# pinball-mega-shield.net
KiCad netlist of a schematic drawn in EAGLE
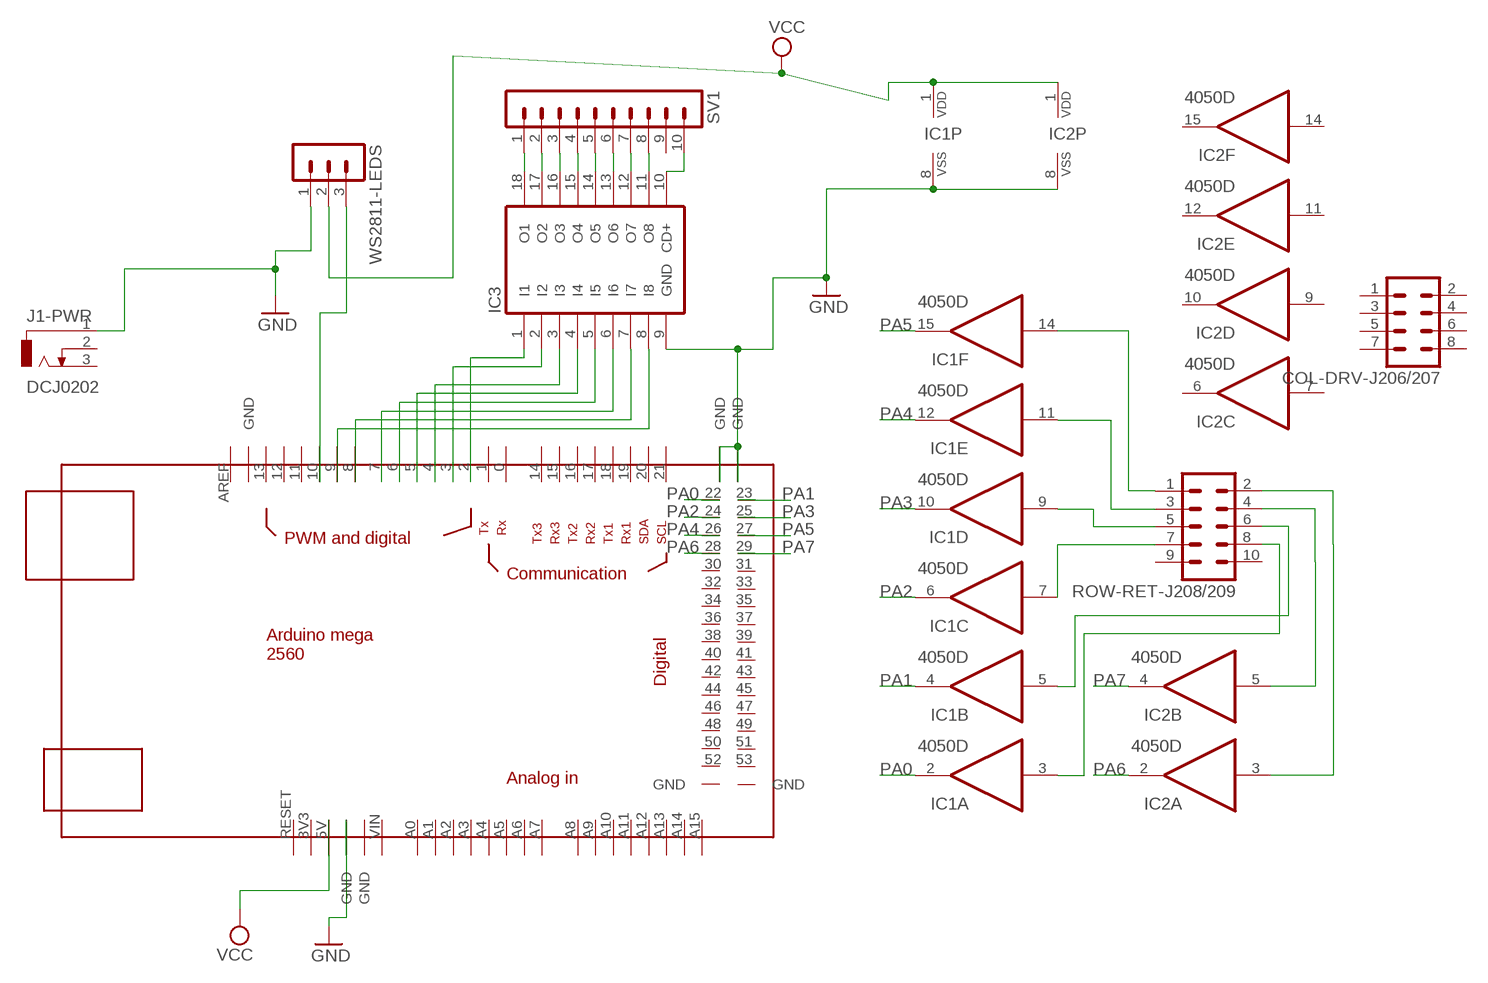
[diagram p0: schematic, sheet 1]

(export (version "E")
  (design (tool "Eeschema 10.0.6"))
  (components
    (comp (ref "COL-DRV-J206/207")
      (value "MA04-2")
      (footprint "eagle-import:MA04-2")
      (libsource (lib "eagle-import") (part "MA04-2"))
    )
    (comp (ref "IC1")
      (value "4050D")
      (footprint "eagle-import:SO16")
      (libsource (lib "eagle-import") (part "4050D"))
    )
    (comp (ref "IC2")
      (value "4050D")
      (footprint "eagle-import:SO16")
      (libsource (lib "eagle-import") (part "4050D"))
    )
    (comp (ref "IC3")
      (value "ULN2803A")
      (footprint "eagle-import:DIL18")
      (libsource (lib "eagle-import") (part "ULN2803A"))
    )
    (comp (ref "J1-PWR")
      (value "DCJ0202")
      (footprint "eagle-import:DCJ0202")
      (libsource (lib "eagle-import") (part "DCJ0202"))
    )
    (comp (ref "ROW-RET-J208/209")
      (value "MA05-2")
      (footprint "eagle-import:MA05-2")
      (libsource (lib "eagle-import") (part "MA05-2"))
    )
    (comp (ref "SV1")
      (value "MA10-1")
      (footprint "eagle-import:MA10-1")
      (libsource (lib "eagle-import") (part "MA10-1"))
    )
    (comp (ref "U$1")
      (value "MEGA_DEVICE")
      (footprint "eagle-import:MEGAOUTLINE")
      (libsource (lib "eagle-import") (part "MEGA_DEVICE"))
    )
    (comp (ref "WS2811-LEDS")
      (value "MA03-1")
      (footprint "eagle-import:MA03-1")
      (libsource (lib "eagle-import") (part "MA03-1"))
    )
  )
  (nets
    (net (code "1") (name "/PA0") (class "Default")
      (node (ref "IC1") (pin "2") (pinfunction "O_2") (pintype "output"))
      (node (ref "U$1") (pin "22") (pinfunction "22_22") (pintype "bidirectional"))
    )
    (net (code "2") (name "/PA1") (class "Default")
      (node (ref "IC1") (pin "4") (pinfunction "O_4") (pintype "output"))
      (node (ref "U$1") (pin "23") (pinfunction "23_23") (pintype "bidirectional"))
    )
    (net (code "3") (name "/PA2") (class "Default")
      (node (ref "IC1") (pin "6") (pinfunction "O_6") (pintype "output"))
      (node (ref "U$1") (pin "24") (pinfunction "24_24") (pintype "bidirectional"))
    )
    (net (code "4") (name "/PA3") (class "Default")
      (node (ref "IC1") (pin "10") (pinfunction "O_10") (pintype "output"))
      (node (ref "U$1") (pin "25") (pinfunction "25_25") (pintype "bidirectional"))
    )
    (net (code "5") (name "/PA4") (class "Default")
      (node (ref "IC1") (pin "12") (pinfunction "O_12") (pintype "output"))
      (node (ref "U$1") (pin "26") (pinfunction "26_26") (pintype "bidirectional"))
    )
    (net (code "6") (name "/PA5") (class "Default")
      (node (ref "IC1") (pin "15") (pinfunction "O_15") (pintype "output"))
      (node (ref "U$1") (pin "27") (pinfunction "27_27") (pintype "bidirectional"))
    )
    (net (code "7") (name "/PA6") (class "Default")
      (node (ref "IC2") (pin "2") (pinfunction "O_2") (pintype "output"))
      (node (ref "U$1") (pin "28") (pinfunction "28_28") (pintype "bidirectional"))
    )
    (net (code "8") (name "/PA7") (class "Default")
      (node (ref "IC2") (pin "4") (pinfunction "O_4") (pintype "output"))
      (node (ref "U$1") (pin "29") (pinfunction "29_29") (pintype "bidirectional"))
    )
    (net (code "9") (name "GND") (class "Default")
      (node (ref "IC1") (pin "8") (pinfunction "VSS_8") (pintype "power_in"))
      (node (ref "IC2") (pin "8") (pinfunction "VSS_8") (pintype "power_in"))
      (node (ref "IC3") (pin "9") (pinfunction "GND_9") (pintype "power_in"))
      (node (ref "J1-PWR") (pin "1") (pinfunction "1_1") (pintype "passive"))
      (node (ref "U$1") (pin "GND@2") (pinfunction "GND_GND@2") (pintype "bidirectional"))
      (node (ref "U$1") (pin "GND@4") (pinfunction "GND_GND@4") (pintype "bidirectional"))
      (node (ref "U$1") (pin "GND@5") (pinfunction "GND_GND@5") (pintype "bidirectional"))
      (node (ref "WS2811-LEDS") (pin "1") (pinfunction "1_1") (pintype "passive"))
    )
    (net (code "10") (name "Net-(IC1A-I)") (class "Default")
      (node (ref "IC1") (pin "3") (pinfunction "I_3") (pintype "input"))
      (node (ref "ROW-RET-J208/209") (pin "8") (pinfunction "8_8") (pintype "passive"))
    )
    (net (code "11") (name "Net-(IC1B-I)") (class "Default")
      (node (ref "IC1") (pin "5") (pinfunction "I_5") (pintype "input"))
      (node (ref "ROW-RET-J208/209") (pin "6") (pinfunction "6_6") (pintype "passive"))
    )
    (net (code "12") (name "Net-(IC1C-I)") (class "Default")
      (node (ref "IC1") (pin "7") (pinfunction "I_7") (pintype "input"))
      (node (ref "ROW-RET-J208/209") (pin "7") (pinfunction "7_7") (pintype "passive"))
    )
    (net (code "13") (name "Net-(IC1D-I)") (class "Default")
      (node (ref "IC1") (pin "9") (pinfunction "I_9") (pintype "input"))
      (node (ref "ROW-RET-J208/209") (pin "5") (pinfunction "5_5") (pintype "passive"))
    )
    (net (code "14") (name "Net-(IC1E-I)") (class "Default")
      (node (ref "IC1") (pin "11") (pinfunction "I_11") (pintype "input"))
      (node (ref "ROW-RET-J208/209") (pin "3") (pinfunction "3_3") (pintype "passive"))
    )
    (net (code "15") (name "Net-(IC1F-I)") (class "Default")
      (node (ref "IC1") (pin "14") (pinfunction "I_14") (pintype "input"))
      (node (ref "ROW-RET-J208/209") (pin "1") (pinfunction "1_1") (pintype "passive"))
    )
    (net (code "16") (name "Net-(IC2A-I)") (class "Default")
      (node (ref "IC2") (pin "3") (pinfunction "I_3") (pintype "input"))
      (node (ref "ROW-RET-J208/209") (pin "2") (pinfunction "2_2") (pintype "passive"))
    )
    (net (code "17") (name "Net-(IC2B-I)") (class "Default")
      (node (ref "IC2") (pin "5") (pinfunction "I_5") (pintype "input"))
      (node (ref "ROW-RET-J208/209") (pin "4") (pinfunction "4_4") (pintype "passive"))
    )
    (net (code "18") (name "Net-(IC3-CD+)") (class "Default")
      (node (ref "IC3") (pin "10") (pinfunction "CD+_10") (pintype "passive"))
      (node (ref "SV1") (pin "10") (pinfunction "10_10") (pintype "passive"))
    )
    (net (code "19") (name "Net-(IC3-I1)") (class "Default")
      (node (ref "IC3") (pin "1") (pinfunction "I1_1") (pintype "input"))
      (node (ref "U$1") (pin "2") (pinfunction "2_2") (pintype "bidirectional"))
    )
    (net (code "20") (name "Net-(IC3-I2)") (class "Default")
      (node (ref "IC3") (pin "2") (pinfunction "I2_2") (pintype "input"))
      (node (ref "U$1") (pin "3") (pinfunction "3_3") (pintype "bidirectional"))
    )
    (net (code "21") (name "Net-(IC3-I3)") (class "Default")
      (node (ref "IC3") (pin "3") (pinfunction "I3_3") (pintype "input"))
      (node (ref "U$1") (pin "4") (pinfunction "4_4") (pintype "bidirectional"))
    )
    (net (code "22") (name "Net-(IC3-I4)") (class "Default")
      (node (ref "IC3") (pin "4") (pinfunction "I4_4") (pintype "input"))
      (node (ref "U$1") (pin "5") (pinfunction "5_5") (pintype "bidirectional"))
    )
    (net (code "23") (name "Net-(IC3-I5)") (class "Default")
      (node (ref "IC3") (pin "5") (pinfunction "I5_5") (pintype "input"))
      (node (ref "U$1") (pin "6") (pinfunction "6_6") (pintype "bidirectional"))
    )
    (net (code "24") (name "Net-(IC3-I6)") (class "Default")
      (node (ref "IC3") (pin "6") (pinfunction "I6_6") (pintype "input"))
      (node (ref "U$1") (pin "7") (pinfunction "7_7") (pintype "bidirectional"))
    )
    (net (code "25") (name "Net-(IC3-I7)") (class "Default")
      (node (ref "IC3") (pin "7") (pinfunction "I7_7") (pintype "input"))
      (node (ref "U$1") (pin "8") (pinfunction "8_8") (pintype "bidirectional"))
    )
    (net (code "26") (name "Net-(IC3-I8)") (class "Default")
      (node (ref "IC3") (pin "8") (pinfunction "I8_8") (pintype "input"))
      (node (ref "U$1") (pin "9") (pinfunction "9_9") (pintype "bidirectional"))
    )
    (net (code "27") (name "Net-(IC3-O1)") (class "Default")
      (node (ref "IC3") (pin "18") (pinfunction "O1_18") (pintype "open_collector"))
      (node (ref "SV1") (pin "1") (pinfunction "1_1") (pintype "passive"))
    )
    (net (code "28") (name "Net-(IC3-O2)") (class "Default")
      (node (ref "IC3") (pin "17") (pinfunction "O2_17") (pintype "open_collector"))
      (node (ref "SV1") (pin "2") (pinfunction "2_2") (pintype "passive"))
    )
    (net (code "29") (name "Net-(IC3-O3)") (class "Default")
      (node (ref "IC3") (pin "16") (pinfunction "O3_16") (pintype "open_collector"))
      (node (ref "SV1") (pin "3") (pinfunction "3_3") (pintype "passive"))
    )
    (net (code "30") (name "Net-(IC3-O4)") (class "Default")
      (node (ref "IC3") (pin "15") (pinfunction "O4_15") (pintype "open_collector"))
      (node (ref "SV1") (pin "4") (pinfunction "4_4") (pintype "passive"))
    )
    (net (code "31") (name "Net-(IC3-O5)") (class "Default")
      (node (ref "IC3") (pin "14") (pinfunction "O5_14") (pintype "open_collector"))
      (node (ref "SV1") (pin "5") (pinfunction "5_5") (pintype "passive"))
    )
    (net (code "32") (name "Net-(IC3-O6)") (class "Default")
      (node (ref "IC3") (pin "13") (pinfunction "O6_13") (pintype "open_collector"))
      (node (ref "SV1") (pin "6") (pinfunction "6_6") (pintype "passive"))
    )
    (net (code "33") (name "Net-(IC3-O7)") (class "Default")
      (node (ref "IC3") (pin "12") (pinfunction "O7_12") (pintype "open_collector"))
      (node (ref "SV1") (pin "7") (pinfunction "7_7") (pintype "passive"))
    )
    (net (code "34") (name "Net-(IC3-O8)") (class "Default")
      (node (ref "IC3") (pin "11") (pinfunction "O8_11") (pintype "open_collector"))
      (node (ref "SV1") (pin "8") (pinfunction "8_8") (pintype "passive"))
    )
    (net (code "35") (name "Net-(U$1-Pad10)") (class "Default")
      (node (ref "U$1") (pin "10") (pinfunction "10_10") (pintype "bidirectional"))
      (node (ref "WS2811-LEDS") (pin "3") (pinfunction "3_3") (pintype "passive"))
    )
    (net (code "36") (name "VCC") (class "Default")
      (node (ref "IC1") (pin "1") (pinfunction "VDD_1") (pintype "power_in"))
      (node (ref "IC2") (pin "1") (pinfunction "VDD_1") (pintype "power_in"))
      (node (ref "U$1") (pin "5V") (pinfunction "5V_5V") (pintype "bidirectional"))
      (node (ref "WS2811-LEDS") (pin "2") (pinfunction "2_2") (pintype "passive"))
    )
    (net (code "37") (name "unconnected-(COL-DRV-J206/207-Pad1)") (class "Default")
      (node (ref "COL-DRV-J206/207") (pin "1") (pinfunction "1_1") (pintype "passive"))
    )
    (net (code "38") (name "unconnected-(COL-DRV-J206/207-Pad2)") (class "Default")
      (node (ref "COL-DRV-J206/207") (pin "2") (pinfunction "2_2") (pintype "passive"))
    )
    (net (code "39") (name "unconnected-(COL-DRV-J206/207-Pad3)") (class "Default")
      (node (ref "COL-DRV-J206/207") (pin "3") (pinfunction "3_3") (pintype "passive"))
    )
    (net (code "40") (name "unconnected-(COL-DRV-J206/207-Pad4)") (class "Default")
      (node (ref "COL-DRV-J206/207") (pin "4") (pinfunction "4_4") (pintype "passive"))
    )
    (net (code "41") (name "unconnected-(COL-DRV-J206/207-Pad5)") (class "Default")
      (node (ref "COL-DRV-J206/207") (pin "5") (pinfunction "5_5") (pintype "passive"))
    )
    (net (code "42") (name "unconnected-(COL-DRV-J206/207-Pad6)") (class "Default")
      (node (ref "COL-DRV-J206/207") (pin "6") (pinfunction "6_6") (pintype "passive"))
    )
    (net (code "43") (name "unconnected-(COL-DRV-J206/207-Pad7)") (class "Default")
      (node (ref "COL-DRV-J206/207") (pin "7") (pinfunction "7_7") (pintype "passive"))
    )
    (net (code "44") (name "unconnected-(COL-DRV-J206/207-Pad8)") (class "Default")
      (node (ref "COL-DRV-J206/207") (pin "8") (pinfunction "8_8") (pintype "passive"))
    )
    (net (code "45") (name "unconnected-(IC2C-I-Pad7)") (class "Default")
      (node (ref "IC2") (pin "7") (pinfunction "I_7") (pintype "input"))
    )
    (net (code "46") (name "unconnected-(IC2C-O-Pad6)") (class "Default")
      (node (ref "IC2") (pin "6") (pinfunction "O_6") (pintype "output"))
    )
    (net (code "47") (name "unconnected-(IC2D-I-Pad9)") (class "Default")
      (node (ref "IC2") (pin "9") (pinfunction "I_9") (pintype "input"))
    )
    (net (code "48") (name "unconnected-(IC2D-O-Pad10)") (class "Default")
      (node (ref "IC2") (pin "10") (pinfunction "O_10") (pintype "output"))
    )
    (net (code "49") (name "unconnected-(IC2E-I-Pad11)") (class "Default")
      (node (ref "IC2") (pin "11") (pinfunction "I_11") (pintype "input"))
    )
    (net (code "50") (name "unconnected-(IC2E-O-Pad12)") (class "Default")
      (node (ref "IC2") (pin "12") (pinfunction "O_12") (pintype "output"))
    )
    (net (code "51") (name "unconnected-(IC2F-I-Pad14)") (class "Default")
      (node (ref "IC2") (pin "14") (pinfunction "I_14") (pintype "input"))
    )
    (net (code "52") (name "unconnected-(IC2F-O-Pad15)") (class "Default")
      (node (ref "IC2") (pin "15") (pinfunction "O_15") (pintype "output"))
    )
    (net (code "53") (name "unconnected-(J1-PWR-Pad2)") (class "Default")
      (node (ref "J1-PWR") (pin "2") (pinfunction "2_2") (pintype "passive"))
    )
    (net (code "54") (name "unconnected-(J1-PWR-Pad3)") (class "Default")
      (node (ref "J1-PWR") (pin "3") (pinfunction "3_3") (pintype "passive"))
    )
    (net (code "55") (name "unconnected-(ROW-RET-J208/209-Pad9)") (class "Default")
      (node (ref "ROW-RET-J208/209") (pin "9") (pinfunction "9_9") (pintype "passive"))
    )
    (net (code "56") (name "unconnected-(ROW-RET-J208/209-Pad10)") (class "Default")
      (node (ref "ROW-RET-J208/209") (pin "10") (pinfunction "10_10") (pintype "passive"))
    )
    (net (code "57") (name "unconnected-(SV1-Pad9)") (class "Default")
      (node (ref "SV1") (pin "9") (pinfunction "9_9") (pintype "passive"))
    )
    (net (code "58") (name "unconnected-(U$1-GND-PadGND@1)") (class "Default")
      (node (ref "U$1") (pin "GND@1") (pinfunction "GND_GND@1") (pintype "bidirectional"))
    )
    (net (code "59") (name "unconnected-(U$1-GND-PadGND@3)") (class "Default")
      (node (ref "U$1") (pin "GND@3") (pinfunction "GND_GND@3") (pintype "bidirectional"))
    )
    (net (code "60") (name "unconnected-(U$1-GND-PadGND@6)") (class "Default")
      (node (ref "U$1") (pin "GND@6") (pinfunction "GND_GND@6") (pintype "bidirectional"))
    )
    (net (code "61") (name "unconnected-(U$1-GND-PadGND@7)") (class "Default")
      (node (ref "U$1") (pin "GND@7") (pinfunction "GND_GND@7") (pintype "bidirectional"))
    )
    (net (code "62") (name "unconnected-(U$1-Pad0)") (class "Default")
      (node (ref "U$1") (pin "0") (pinfunction "0_0") (pintype "bidirectional"))
    )
    (net (code "63") (name "unconnected-(U$1-Pad1)") (class "Default")
      (node (ref "U$1") (pin "1") (pinfunction "1_1") (pintype "bidirectional"))
    )
    (net (code "64") (name "unconnected-(U$1-Pad3V3)") (class "Default")
      (node (ref "U$1") (pin "3V3") (pinfunction "3V3_3V3") (pintype "bidirectional"))
    )
    (net (code "65") (name "unconnected-(U$1-Pad11)") (class "Default")
      (node (ref "U$1") (pin "11") (pinfunction "11_11") (pintype "bidirectional"))
    )
    (net (code "66") (name "unconnected-(U$1-Pad12)") (class "Default")
      (node (ref "U$1") (pin "12") (pinfunction "12_12") (pintype "bidirectional"))
    )
    (net (code "67") (name "unconnected-(U$1-Pad13)") (class "Default")
      (node (ref "U$1") (pin "13") (pinfunction "13_13") (pintype "bidirectional"))
    )
    (net (code "68") (name "unconnected-(U$1-Pad14)") (class "Default")
      (node (ref "U$1") (pin "14") (pinfunction "14_14") (pintype "bidirectional"))
    )
    (net (code "69") (name "unconnected-(U$1-Pad15)") (class "Default")
      (node (ref "U$1") (pin "15") (pinfunction "15_15") (pintype "bidirectional"))
    )
    (net (code "70") (name "unconnected-(U$1-Pad16)") (class "Default")
      (node (ref "U$1") (pin "16") (pinfunction "16_16") (pintype "bidirectional"))
    )
    (net (code "71") (name "unconnected-(U$1-Pad17)") (class "Default")
      (node (ref "U$1") (pin "17") (pinfunction "17_17") (pintype "bidirectional"))
    )
    (net (code "72") (name "unconnected-(U$1-Pad18)") (class "Default")
      (node (ref "U$1") (pin "18") (pinfunction "18_18") (pintype "bidirectional"))
    )
    (net (code "73") (name "unconnected-(U$1-Pad19)") (class "Default")
      (node (ref "U$1") (pin "19") (pinfunction "19_19") (pintype "bidirectional"))
    )
    (net (code "74") (name "unconnected-(U$1-Pad20)") (class "Default")
      (node (ref "U$1") (pin "20") (pinfunction "20_20") (pintype "bidirectional"))
    )
    (net (code "75") (name "unconnected-(U$1-Pad21)") (class "Default")
      (node (ref "U$1") (pin "21") (pinfunction "21_21") (pintype "bidirectional"))
    )
    (net (code "76") (name "unconnected-(U$1-Pad30)") (class "Default")
      (node (ref "U$1") (pin "30") (pinfunction "30_30") (pintype "bidirectional"))
    )
    (net (code "77") (name "unconnected-(U$1-Pad31)") (class "Default")
      (node (ref "U$1") (pin "31") (pinfunction "31_31") (pintype "bidirectional"))
    )
    (net (code "78") (name "unconnected-(U$1-Pad32)") (class "Default")
      (node (ref "U$1") (pin "32") (pinfunction "32_32") (pintype "bidirectional"))
    )
    (net (code "79") (name "unconnected-(U$1-Pad33)") (class "Default")
      (node (ref "U$1") (pin "33") (pinfunction "33_33") (pintype "bidirectional"))
    )
    (net (code "80") (name "unconnected-(U$1-Pad34)") (class "Default")
      (node (ref "U$1") (pin "34") (pinfunction "34_34") (pintype "bidirectional"))
    )
    (net (code "81") (name "unconnected-(U$1-Pad35)") (class "Default")
      (node (ref "U$1") (pin "35") (pinfunction "35_35") (pintype "bidirectional"))
    )
    (net (code "82") (name "unconnected-(U$1-Pad36)") (class "Default")
      (node (ref "U$1") (pin "36") (pinfunction "36_36") (pintype "bidirectional"))
    )
    (net (code "83") (name "unconnected-(U$1-Pad37)") (class "Default")
      (node (ref "U$1") (pin "37") (pinfunction "37_37") (pintype "bidirectional"))
    )
    (net (code "84") (name "unconnected-(U$1-Pad38)") (class "Default")
      (node (ref "U$1") (pin "38") (pinfunction "38_38") (pintype "bidirectional"))
    )
    (net (code "85") (name "unconnected-(U$1-Pad39)") (class "Default")
      (node (ref "U$1") (pin "39") (pinfunction "39_39") (pintype "bidirectional"))
    )
    (net (code "86") (name "unconnected-(U$1-Pad40)") (class "Default")
      (node (ref "U$1") (pin "40") (pinfunction "40_40") (pintype "bidirectional"))
    )
    (net (code "87") (name "unconnected-(U$1-Pad41)") (class "Default")
      (node (ref "U$1") (pin "41") (pinfunction "41_41") (pintype "bidirectional"))
    )
    (net (code "88") (name "unconnected-(U$1-Pad42)") (class "Default")
      (node (ref "U$1") (pin "42") (pinfunction "42_42") (pintype "bidirectional"))
    )
    (net (code "89") (name "unconnected-(U$1-Pad43)") (class "Default")
      (node (ref "U$1") (pin "43") (pinfunction "43_43") (pintype "bidirectional"))
    )
    (net (code "90") (name "unconnected-(U$1-Pad44)") (class "Default")
      (node (ref "U$1") (pin "44") (pinfunction "44_44") (pintype "bidirectional"))
    )
    (net (code "91") (name "unconnected-(U$1-Pad45)") (class "Default")
      (node (ref "U$1") (pin "45") (pinfunction "45_45") (pintype "bidirectional"))
    )
    (net (code "92") (name "unconnected-(U$1-Pad46)") (class "Default")
      (node (ref "U$1") (pin "46") (pinfunction "46_46") (pintype "bidirectional"))
    )
    (net (code "93") (name "unconnected-(U$1-Pad47)") (class "Default")
      (node (ref "U$1") (pin "47") (pinfunction "47_47") (pintype "bidirectional"))
    )
    (net (code "94") (name "unconnected-(U$1-Pad48)") (class "Default")
      (node (ref "U$1") (pin "48") (pinfunction "48_48") (pintype "bidirectional"))
    )
    (net (code "95") (name "unconnected-(U$1-Pad49)") (class "Default")
      (node (ref "U$1") (pin "49") (pinfunction "49_49") (pintype "bidirectional"))
    )
    (net (code "96") (name "unconnected-(U$1-Pad50)") (class "Default")
      (node (ref "U$1") (pin "50") (pinfunction "50_50") (pintype "bidirectional"))
    )
    (net (code "97") (name "unconnected-(U$1-Pad51)") (class "Default")
      (node (ref "U$1") (pin "51") (pinfunction "51_51") (pintype "bidirectional"))
    )
    (net (code "98") (name "unconnected-(U$1-Pad52)") (class "Default")
      (node (ref "U$1") (pin "52") (pinfunction "52_52") (pintype "bidirectional"))
    )
    (net (code "99") (name "unconnected-(U$1-Pad53)") (class "Default")
      (node (ref "U$1") (pin "53") (pinfunction "53_53") (pintype "bidirectional"))
    )
    (net (code "100") (name "unconnected-(U$1-PadA0)") (class "Default")
      (node (ref "U$1") (pin "A0") (pinfunction "A0_A0") (pintype "bidirectional"))
    )
    (net (code "101") (name "unconnected-(U$1-PadA1)") (class "Default")
      (node (ref "U$1") (pin "A1") (pinfunction "A1_A1") (pintype "bidirectional"))
    )
    (net (code "102") (name "unconnected-(U$1-PadA2)") (class "Default")
      (node (ref "U$1") (pin "A2") (pinfunction "A2_A2") (pintype "bidirectional"))
    )
    (net (code "103") (name "unconnected-(U$1-PadA3)") (class "Default")
      (node (ref "U$1") (pin "A3") (pinfunction "A3_A3") (pintype "bidirectional"))
    )
    (net (code "104") (name "unconnected-(U$1-PadA4)") (class "Default")
      (node (ref "U$1") (pin "A4") (pinfunction "A4_A4") (pintype "bidirectional"))
    )
    (net (code "105") (name "unconnected-(U$1-PadA5)") (class "Default")
      (node (ref "U$1") (pin "A5") (pinfunction "A5_A5") (pintype "bidirectional"))
    )
    (net (code "106") (name "unconnected-(U$1-PadA6)") (class "Default")
      (node (ref "U$1") (pin "A6") (pinfunction "A6_A6") (pintype "bidirectional"))
    )
    (net (code "107") (name "unconnected-(U$1-PadA7)") (class "Default")
      (node (ref "U$1") (pin "A7") (pinfunction "A7_A7") (pintype "bidirectional"))
    )
    (net (code "108") (name "unconnected-(U$1-PadA8)") (class "Default")
      (node (ref "U$1") (pin "A8") (pinfunction "A8_A8") (pintype "bidirectional"))
    )
    (net (code "109") (name "unconnected-(U$1-PadA9)") (class "Default")
      (node (ref "U$1") (pin "A9") (pinfunction "A9_A9") (pintype "bidirectional"))
    )
    (net (code "110") (name "unconnected-(U$1-PadA10)") (class "Default")
      (node (ref "U$1") (pin "A10") (pinfunction "A10_A10") (pintype "bidirectional"))
    )
    (net (code "111") (name "unconnected-(U$1-PadA11)") (class "Default")
      (node (ref "U$1") (pin "A11") (pinfunction "A11_A11") (pintype "bidirectional"))
    )
    (net (code "112") (name "unconnected-(U$1-PadA12)") (class "Default")
      (node (ref "U$1") (pin "A12") (pinfunction "A12_A12") (pintype "bidirectional"))
    )
    (net (code "113") (name "unconnected-(U$1-PadA13)") (class "Default")
      (node (ref "U$1") (pin "A13") (pinfunction "A13_A13") (pintype "bidirectional"))
    )
    (net (code "114") (name "unconnected-(U$1-PadA14)") (class "Default")
      (node (ref "U$1") (pin "A14") (pinfunction "A14_A14") (pintype "bidirectional"))
    )
    (net (code "115") (name "unconnected-(U$1-PadA15)") (class "Default")
      (node (ref "U$1") (pin "A15") (pinfunction "A15_A15") (pintype "bidirectional"))
    )
    (net (code "116") (name "unconnected-(U$1-PadAREF)") (class "Default")
      (node (ref "U$1") (pin "AREF") (pinfunction "AREF_AREF") (pintype "bidirectional"))
    )
    (net (code "117") (name "unconnected-(U$1-PadRESET)") (class "Default")
      (node (ref "U$1") (pin "RESET") (pinfunction "RESET_RESET") (pintype "bidirectional"))
    )
    (net (code "118") (name "unconnected-(U$1-PadVIN)") (class "Default")
      (node (ref "U$1") (pin "VIN") (pinfunction "VIN_VIN") (pintype "bidirectional"))
    )
  )
)
